# Power-Tree-VBATT-Filter.net
KiCad netlist of a schematic drawn in Altium Designer
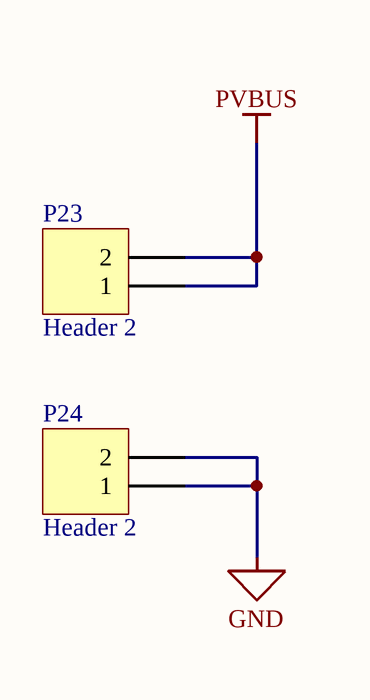
[diagram p0: Power-Tree-VBATT-Filter.SchDoc]

(export (version "E")
  (design (tool "Eeschema 10.0.6"))
  (components
    (comp (ref "P23")
      (value "Header 2")
      (footprint "HDR1X2")
      (description "Header, 2-Pin")
      (fields (field (name "PUBLISHER") "Altium Limited"))
      (libsource (lib "AT-Misc-Connectors") (part "Header 2"))
    )
    (comp (ref "P24")
      (value "Header 2")
      (footprint "HDR1X2")
      (description "Header, 2-Pin")
      (fields (field (name "PUBLISHER") "Altium Limited"))
      (libsource (lib "AT-Misc-Connectors") (part "Header 2"))
    )
  )
  (nets
    (net (code "1") (name "GND") (class "Default")
      (node (ref "P24") (pin "1") (pinfunction "1_1") (pintype "passive"))
      (node (ref "P24") (pin "2") (pinfunction "2_2") (pintype "passive"))
    )
    (net (code "2") (name "PVBUS") (class "Default")
      (node (ref "P23") (pin "1") (pinfunction "1_1") (pintype "passive"))
      (node (ref "P23") (pin "2") (pinfunction "2_2") (pintype "passive"))
    )
  )
)
